# Fri3D_2026_Power.net
KiCad netlist of a schematic drawn in Altium Designer
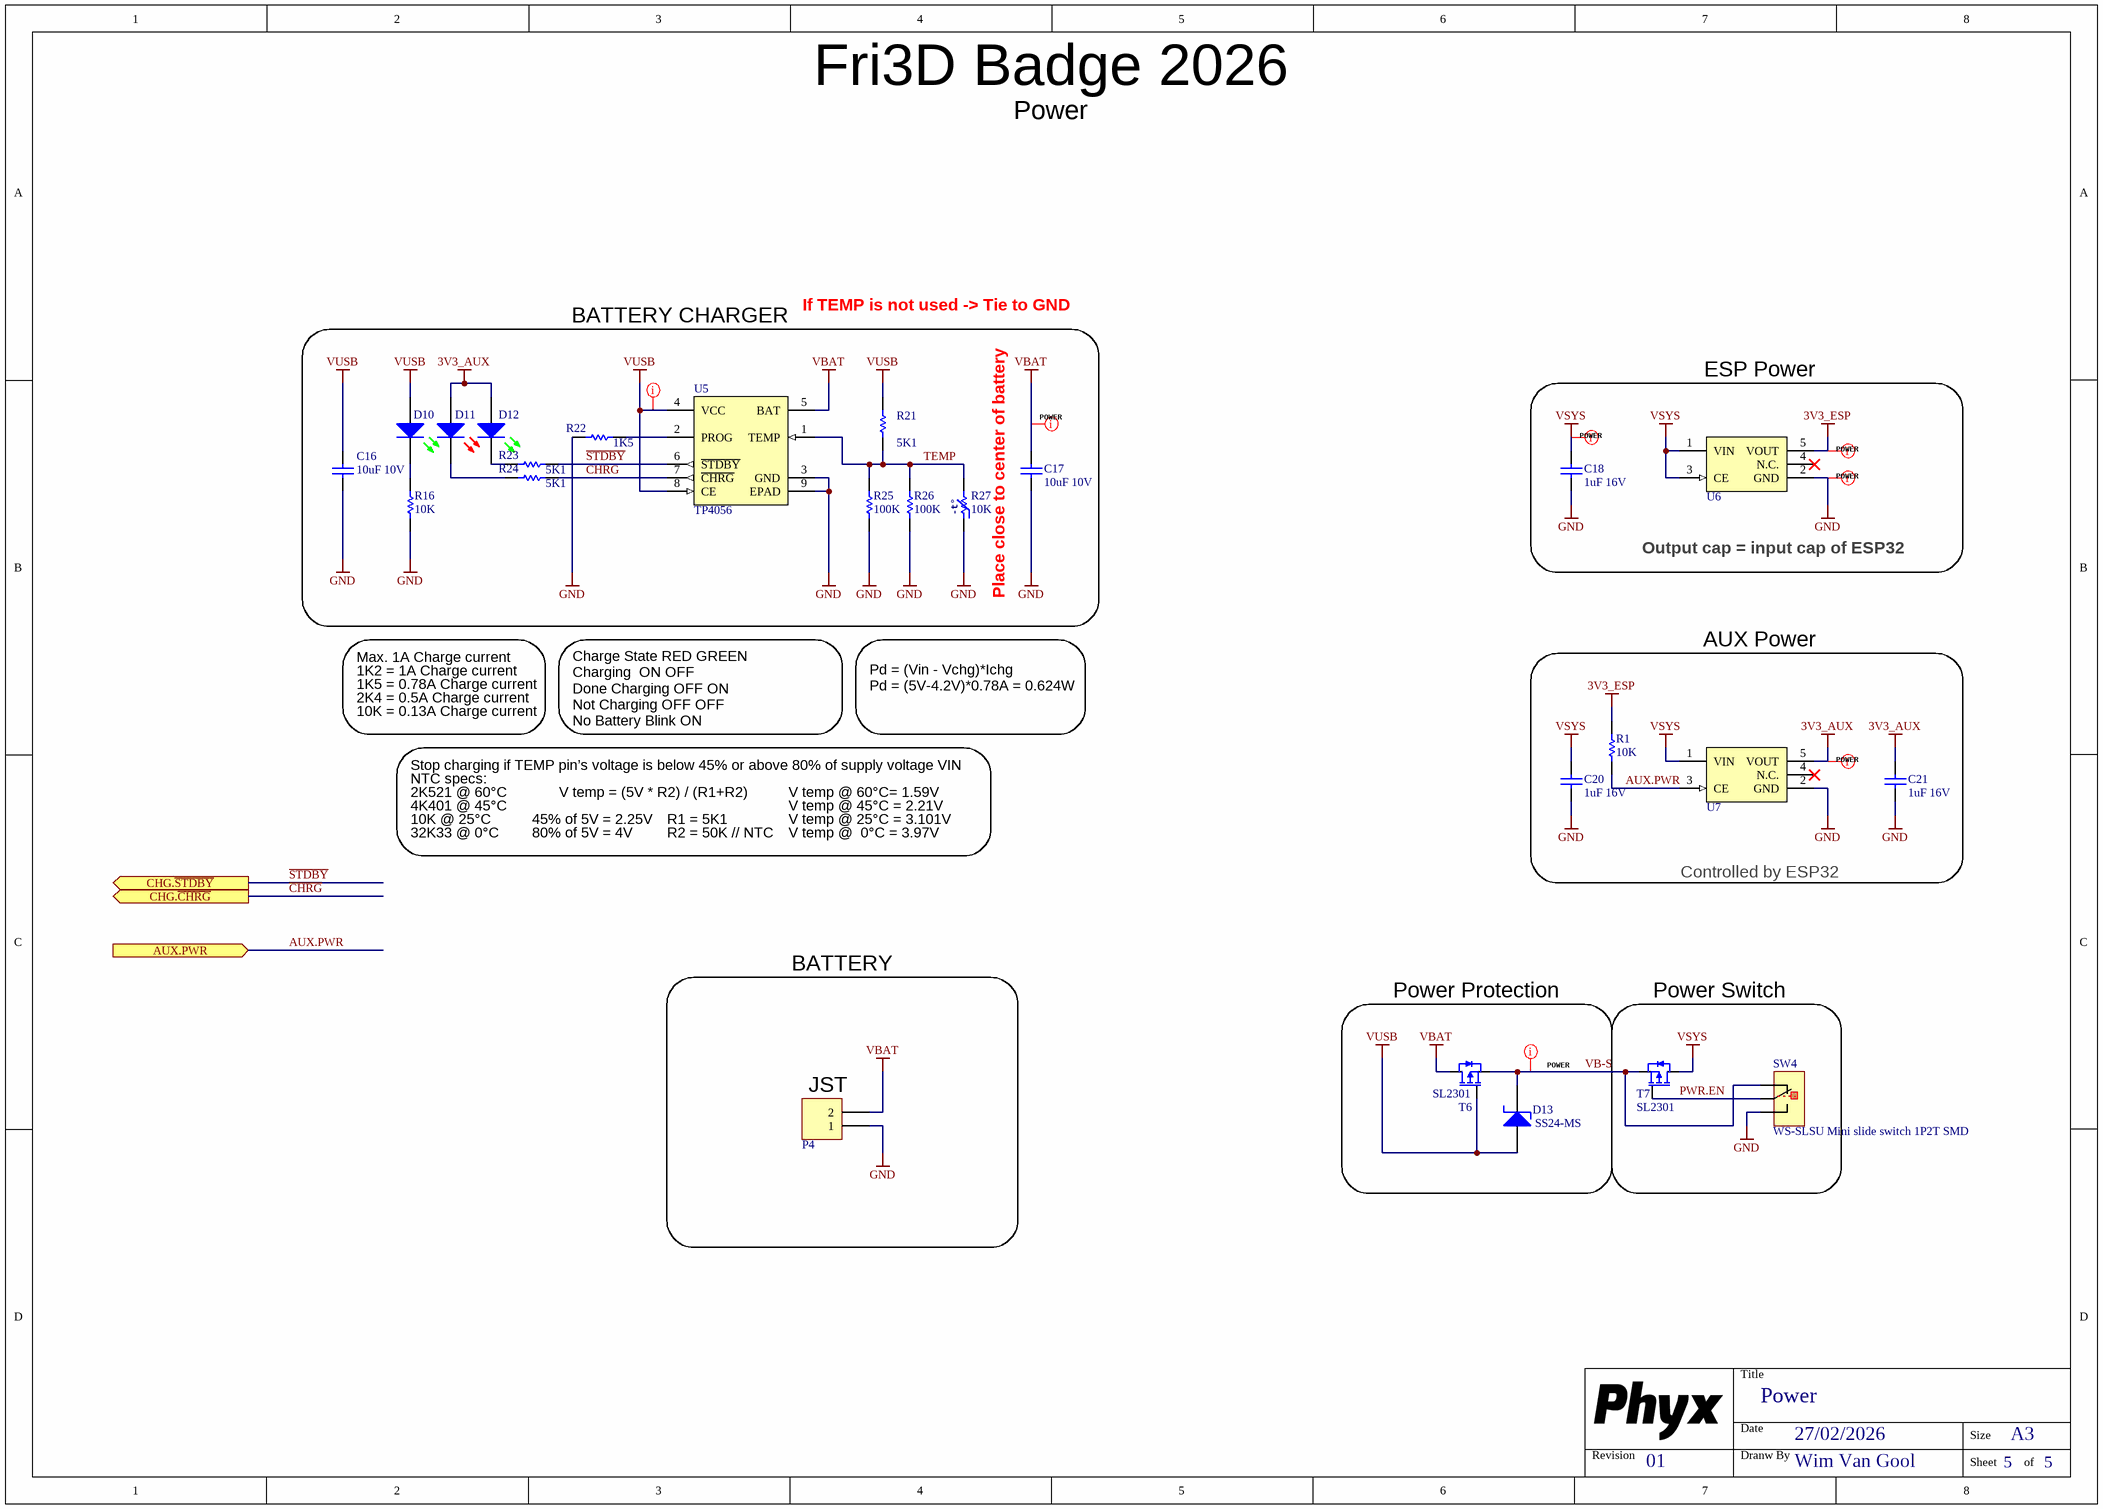
[diagram p0: Fri3D_2026_Power.SchDoc]

(export (version "E")
  (design (tool "Eeschema 10.0.6"))
  (components
    (comp (ref "C16")
      (value "10uF 10V")
      (footprint "C0805_N")
      (description "Capacitor Ceramic")
      (libsource (lib "Phyx_Components") (part "CAP_CERAMIC"))
    )
    (comp (ref "C17")
      (value "10uF 10V")
      (footprint "C0805_N")
      (description "Capacitor Ceramic")
      (libsource (lib "Phyx_Components") (part "CAP_CERAMIC"))
    )
    (comp (ref "C18")
      (value "1uF 16V")
      (footprint "C0603_N")
      (description "Capacitor Ceramic")
      (libsource (lib "Phyx_Components") (part "CAP_CERAMIC"))
    )
    (comp (ref "C20")
      (value "1uF 16V")
      (footprint "C0603_N")
      (description "Capacitor Ceramic")
      (libsource (lib "Phyx_Components") (part "CAP_CERAMIC"))
    )
    (comp (ref "C21")
      (value "1uF 16V")
      (footprint "C0603_N")
      (description "Capacitor Ceramic")
      (libsource (lib "Phyx_Components") (part "CAP_CERAMIC"))
    )
    (comp (ref "D10")
      (value "Default 0805 Green LED")
      (footprint "LED_0805_GR")
      (description "=Description")
      (libsource (lib "Phyx_Components") (part "LED_GREEN"))
    )
    (comp (ref "D11")
      (value "Default 0805 Red LED")
      (footprint "LED_0805_RD")
      (description "=Description")
      (libsource (lib "Phyx_Components") (part "LED_RED"))
    )
    (comp (ref "D12")
      (value "Default 0805 Green LED")
      (footprint "LED_0805_GR")
      (description "=Description")
      (libsource (lib "Phyx_Components") (part "LED_GREEN"))
    )
    (comp (ref "D13")
      (value "SS24-MS")
      (footprint "DO-214AC_AC")
      (description "=Description")
      (fields (field (name "Comment") "40V 2A 550mV@2A DO-214 Schottky"))
      (libsource (lib "Phyx_Components") (part "Schottky_AC"))
    )
    (comp (ref "P4")
      (value "Header RA 1.5mm Shrouded S2B-ZR-SM4A-TF")
      (footprint "JST_ZH_S2B-ZR-SM4A-TF")
      (libsource (lib "Phyx_Components") (part "Header 2"))
    )
    (comp (ref "R1")
      (value "10K")
      (footprint "R0603_N")
      (libsource (lib "Phyx_Components") (part "RESISTOR"))
    )
    (comp (ref "R16")
      (value "10K")
      (footprint "R0603_N")
      (description "RES # 10K 0603")
      (fields (field (name "Comment") "RESISTOR"))
      (libsource (lib "Phyx_Components") (part "RESISTOR"))
    )
    (comp (ref "R21")
      (value "5K1")
      (footprint "R0603_N")
      (libsource (lib "Phyx_Components") (part "RESISTOR"))
    )
    (comp (ref "R22")
      (value "1K5")
      (footprint "R0603_N")
      (libsource (lib "Phyx_Components") (part "RESISTOR"))
    )
    (comp (ref "R23")
      (value "5K1")
      (footprint "R0603_N")
      (libsource (lib "Phyx_Components") (part "RESISTOR"))
    )
    (comp (ref "R24")
      (value "5K1")
      (footprint "R0603_N")
      (libsource (lib "Phyx_Components") (part "RESISTOR"))
    )
    (comp (ref "R25")
      (value "100K")
      (footprint "R0603_N")
      (libsource (lib "Phyx_Components") (part "RESISTOR"))
    )
    (comp (ref "R26")
      (value "100K")
      (footprint "R0603_N")
      (libsource (lib "Phyx_Components") (part "RESISTOR"))
    )
    (comp (ref "R27")
      (value "10K")
      (footprint "R0402")
      (libsource (lib "Phyx_Components") (part "RESISTOR_NTC"))
    )
    (comp (ref "SW4")
      (value "WS-SLSU Mini slide switch 1P2T SMD")
      (footprint "WE_450404015514")
      (libsource (lib "Phyx_Components") (part "SW_1P2T"))
    )
    (comp (ref "T6")
      (value "SL2301")
      (footprint "SOT23-3")
      (description "=Description")
      (fields (field (name "Comment") "-2.3A -20V P-Ch MOSFET Vgs -1V"))
      (libsource (lib "Phyx_Components") (part "P_MOSFET_GSD"))
    )
    (comp (ref "T7")
      (value "SL2301")
      (footprint "SOT23-3")
      (description "=Description")
      (fields (field (name "Comment") "-2.3A -20V P-Ch MOSFET Vgs -1V"))
      (libsource (lib "Phyx_Components") (part "P_MOSFET_GSD"))
    )
    (comp (ref "U5")
      (value "TP4056")
      (footprint "SOIC_N_8_TH")
      (description "=Description")
      (fields (field (name "Comment") "Single Cell LiIon charger max 1A"))
      (libsource (lib "Phyx_Components") (part "TP4056"))
    )
    (comp (ref "U6")
      (value "3V3 LDO 700mA 50mV")
      (footprint "SOT23-5")
      (description "=Designator")
      (libsource (lib "Phyx_Components") (part "XC6210_SOT"))
    )
    (comp (ref "U7")
      (value "3V3 LDO 700mA 50mV")
      (footprint "SOT23-5")
      (description "=Designator")
      (libsource (lib "Phyx_Components") (part "XC6210_SOT"))
    )
  )
  (nets
    (net (code "1") (name "/AUX.PWR") (class "Default")
      (node (ref "R1") (pin "2") (pinfunction "2_2") (pintype "passive"))
      (node (ref "U7") (pin "3") (pinfunction "CE_3") (pintype "input"))
    )
    (net (code "2") (name "/PWR.EN") (class "Default")
      (node (ref "SW4") (pin "2") (pinfunction "2_2") (pintype "passive"))
      (node (ref "T7") (pin "1") (pinfunction "G_1") (pintype "passive"))
    )
    (net (code "3") (name "/TEMP") (class "Default")
      (node (ref "R21") (pin "2") (pinfunction "2_2") (pintype "passive"))
      (node (ref "R25") (pin "1") (pinfunction "1_1") (pintype "passive"))
      (node (ref "R26") (pin "1") (pinfunction "1_1") (pintype "passive"))
      (node (ref "R27") (pin "1") (pinfunction "1_1") (pintype "passive"))
      (node (ref "U5") (pin "1") (pinfunction "TEMP_1") (pintype "input"))
    )
    (net (code "4") (name "/VB-S") (class "Default")
      (node (ref "D13") (pin "C") (pinfunction "C_C") (pintype "passive"))
      (node (ref "SW4") (pin "1") (pinfunction "1_1") (pintype "passive"))
      (node (ref "T6") (pin "2") (pinfunction "S_2") (pintype "passive"))
      (node (ref "T7") (pin "2") (pinfunction "S_2") (pintype "passive"))
    )
    (net (code "5") (name "/~{CHRG}") (class "Default")
      (node (ref "R24") (pin "2") (pinfunction "2_2") (pintype "passive"))
      (node (ref "U5") (pin "7") (pinfunction "~{CHRG}_7") (pintype "output"))
    )
    (net (code "6") (name "/~{STDBY}") (class "Default")
      (node (ref "R23") (pin "2") (pinfunction "2_2") (pintype "passive"))
      (node (ref "U5") (pin "6") (pinfunction "~{STDBY}_6") (pintype "output"))
    )
    (net (code "7") (name "3V3_AUX") (class "Default")
      (node (ref "C21") (pin "1") (pinfunction "1_1") (pintype "passive"))
      (node (ref "D11") (pin "1") (pinfunction "A_1") (pintype "passive"))
      (node (ref "D12") (pin "1") (pinfunction "A_1") (pintype "passive"))
      (node (ref "U7") (pin "5") (pinfunction "VOUT_5") (pintype "power_in"))
    )
    (net (code "8") (name "3V3_ESP") (class "Default")
      (node (ref "R1") (pin "1") (pinfunction "1_1") (pintype "passive"))
      (node (ref "U6") (pin "5") (pinfunction "VOUT_5") (pintype "power_in"))
    )
    (net (code "9") (name "GND") (class "Default")
      (node (ref "C16") (pin "2") (pinfunction "2_2") (pintype "passive"))
      (node (ref "C17") (pin "2") (pinfunction "2_2") (pintype "passive"))
      (node (ref "C18") (pin "2") (pinfunction "2_2") (pintype "passive"))
      (node (ref "C20") (pin "2") (pinfunction "2_2") (pintype "passive"))
      (node (ref "C21") (pin "2") (pinfunction "2_2") (pintype "passive"))
      (node (ref "P4") (pin "1") (pinfunction "1_1") (pintype "passive"))
      (node (ref "R16") (pin "2") (pinfunction "2_2") (pintype "passive"))
      (node (ref "R22") (pin "2") (pinfunction "2_2") (pintype "passive"))
      (node (ref "R25") (pin "2") (pinfunction "2_2") (pintype "passive"))
      (node (ref "R26") (pin "2") (pinfunction "2_2") (pintype "passive"))
      (node (ref "R27") (pin "2") (pinfunction "2_2") (pintype "passive"))
      (node (ref "SW4") (pin "3") (pinfunction "3_3") (pintype "passive"))
      (node (ref "U5") (pin "3") (pinfunction "GND_3") (pintype "power_in"))
      (node (ref "U5") (pin "9") (pinfunction "EPAD_9") (pintype "power_in"))
      (node (ref "U6") (pin "2") (pinfunction "GND_2") (pintype "power_in"))
      (node (ref "U7") (pin "2") (pinfunction "GND_2") (pintype "power_in"))
    )
    (net (code "10") (name "Net-(D10-K)") (class "Default")
      (node (ref "D10") (pin "2") (pinfunction "K_2") (pintype "passive"))
      (node (ref "R16") (pin "1") (pinfunction "1_1") (pintype "passive"))
    )
    (net (code "11") (name "Net-(D11-K)") (class "Default")
      (node (ref "D11") (pin "2") (pinfunction "K_2") (pintype "passive"))
      (node (ref "R24") (pin "1") (pinfunction "1_1") (pintype "passive"))
    )
    (net (code "12") (name "Net-(D12-K)") (class "Default")
      (node (ref "D12") (pin "2") (pinfunction "K_2") (pintype "passive"))
      (node (ref "R23") (pin "1") (pinfunction "1_1") (pintype "passive"))
    )
    (net (code "13") (name "Net-(U5-PROG)") (class "Default")
      (node (ref "R22") (pin "1") (pinfunction "1_1") (pintype "passive"))
      (node (ref "U5") (pin "2") (pinfunction "PROG_2") (pintype "passive"))
    )
    (net (code "14") (name "VBAT") (class "Default")
      (node (ref "C17") (pin "1") (pinfunction "1_1") (pintype "passive"))
      (node (ref "P4") (pin "2") (pinfunction "2_2") (pintype "passive"))
      (node (ref "T6") (pin "3") (pinfunction "D_3") (pintype "passive"))
      (node (ref "U5") (pin "5") (pinfunction "BAT_5") (pintype "power_in"))
    )
    (net (code "15") (name "VSYS") (class "Default")
      (node (ref "C18") (pin "1") (pinfunction "1_1") (pintype "passive"))
      (node (ref "C20") (pin "1") (pinfunction "1_1") (pintype "passive"))
      (node (ref "T7") (pin "3") (pinfunction "D_3") (pintype "passive"))
      (node (ref "U6") (pin "1") (pinfunction "VIN_1") (pintype "power_in"))
      (node (ref "U6") (pin "3") (pinfunction "CE_3") (pintype "input"))
      (node (ref "U7") (pin "1") (pinfunction "VIN_1") (pintype "power_in"))
    )
    (net (code "16") (name "VUSB") (class "Default")
      (node (ref "C16") (pin "1") (pinfunction "1_1") (pintype "passive"))
      (node (ref "D10") (pin "1") (pinfunction "A_1") (pintype "passive"))
      (node (ref "D13") (pin "A") (pinfunction "A_A") (pintype "passive"))
      (node (ref "R21") (pin "1") (pinfunction "1_1") (pintype "passive"))
      (node (ref "T6") (pin "1") (pinfunction "G_1") (pintype "passive"))
      (node (ref "U5") (pin "4") (pinfunction "VCC_4") (pintype "power_in"))
      (node (ref "U5") (pin "8") (pinfunction "CE_8") (pintype "input"))
    )
    (net (code "17") (name "unconnected-(U6-N.C.-Pad4)") (class "Default")
      (node (ref "U6") (pin "4") (pinfunction "N.C._4") (pintype "passive+no_connect"))
    )
    (net (code "18") (name "unconnected-(U7-N.C.-Pad4)") (class "Default")
      (node (ref "U7") (pin "4") (pinfunction "N.C._4") (pintype "passive+no_connect"))
    )
  )
)
